# CAN_ESP.net
KiCad netlist of a schematic drawn in Altium Designer
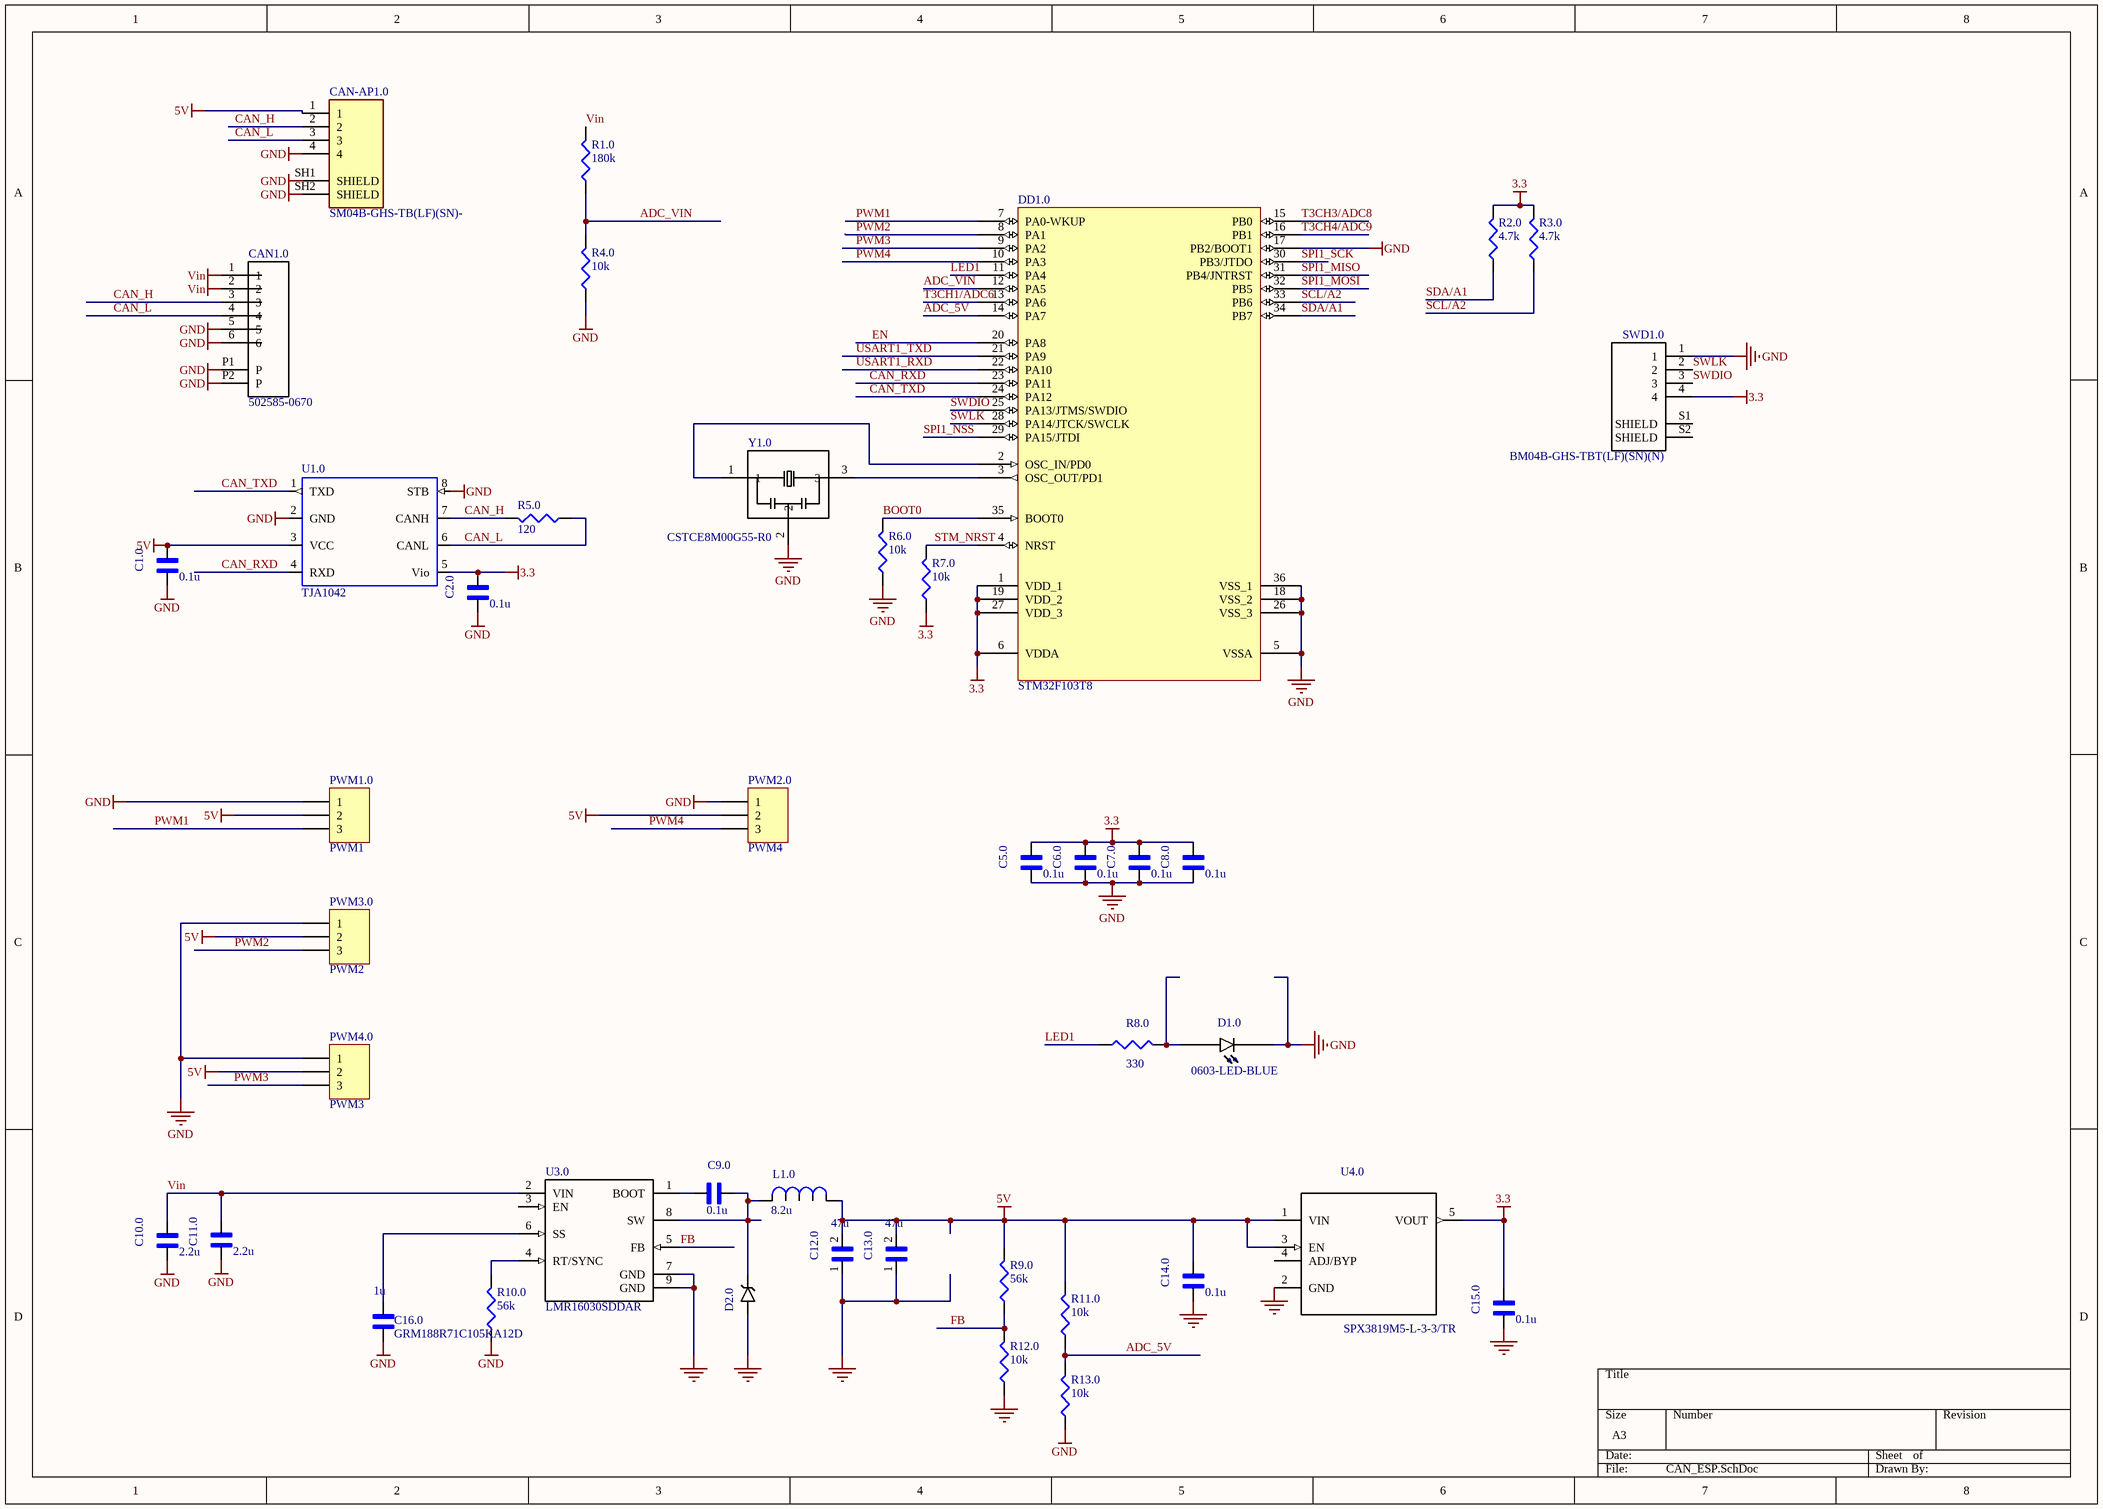
[diagram p0: CAN_ESP.SchDoc]

(export (version "E")
  (design (tool "Eeschema 10.0.6"))
  (components
    (comp (ref "C1.0")
      (value "0.1u")
      (footprint "*CAPC1608X90")
      (description "Cap Thin Film 0.1uf 50v 0603")
      (fields (field (name "MF") "AVX") (field (name "MP") "GX035C104MAT2-500 or CL10B104JB8NNNC"))
      (libsource (lib "lib") (part "GX035C104MAT2-500"))
    )
    (comp (ref "C2.0")
      (value "0.1u")
      (footprint "*CAPC1608X90")
      (description "Cap Thin Film 0.1uf 50v 0603")
      (fields (field (name "MF") "AVX") (field (name "MP") "GX035C104MAT2-500 or CL10B104JB8NNNC"))
      (libsource (lib "lib") (part "GX035C104MAT2-500"))
    )
    (comp (ref "C5.0")
      (value "0.1u")
      (footprint "*CAPC1608X90")
      (description "Cap Thin Film 0.1uf 50v 0603")
      (fields (field (name "MF") "AVX") (field (name "MP") "GX035C104MAT2-500 or CL10B104JB8NNNC"))
      (libsource (lib "lib") (part "GX035C104MAT2-500"))
    )
    (comp (ref "C6.0")
      (value "0.1u")
      (footprint "*CAPC1608X90")
      (description "Cap Thin Film 0.1uf 50v 0603")
      (fields (field (name "MF") "AVX") (field (name "MP") "GX035C104MAT2-500 or CL10B104JB8NNNC"))
      (libsource (lib "lib") (part "GX035C104MAT2-500"))
    )
    (comp (ref "C7.0")
      (value "0.1u")
      (footprint "*CAPC1608X90")
      (description "Cap Thin Film 0.1uf 50v 0603")
      (fields (field (name "MF") "AVX") (field (name "MP") "GX035C104MAT2-500 or CL10B104JB8NNNC"))
      (libsource (lib "lib") (part "GX035C104MAT2-500"))
    )
    (comp (ref "C8.0")
      (value "0.1u")
      (footprint "*CAPC1608X90")
      (description "Cap Thin Film 0.1uf 50v 0603")
      (fields (field (name "MF") "AVX") (field (name "MP") "GX035C104MAT2-500 or CL10B104JB8NNNC"))
      (libsource (lib "lib") (part "GX035C104MAT2-500"))
    )
    (comp (ref "C9.0")
      (value "0.1u")
      (footprint "*CAPC1608X90")
      (description "Cap Thin Film 0.1uf 50v 0603")
      (fields (field (name "MF") "AVX") (field (name "MP") "GX035C104MAT2-500 or CL10B104JB8NNNC"))
      (libsource (lib "lib") (part "GX035C104MAT2-500"))
    )
    (comp (ref "C10.0")
      (value "2.2u")
      (footprint "*CAP3216X125N")
      (description "1206 2.2 uF 50 V В±10% Tolerance X7R SMT Multilayer Ceramic Capacitor")
      (fields (field (name "MF") "Murata Electronics") (field (name "MP") "GRM31CR71H225KA88L"))
      (libsource (lib "lib") (part "GRM31CR71H225KA88L"))
    )
    (comp (ref "C11.0")
      (value "2.2u")
      (footprint "*CAP3216X125N")
      (description "1206 2.2 uF 50 V В±10% Tolerance X7R SMT Multilayer Ceramic Capacitor")
      (fields (field (name "MF") "Murata Electronics") (field (name "MP") "GRM31CR71H225KA88L"))
      (libsource (lib "lib") (part "GRM31CR71H225KA88L"))
    )
    (comp (ref "C12.0")
      (value "47u")
      (footprint "*CAPC3216X125N")
      (description "Multilayer Ceramic Capacitor, GRM Series, 47 - F, - 10%, X5R, 10 V, 1206 [3216 Metric]")
      (fields (field (name "MF") "Murata Electronics") (field (name "MP") "GRM31CR61A476KE15L"))
      (libsource (lib "lib") (part "GRM31CR61A476KE15L"))
    )
    (comp (ref "C13.0")
      (value "47u")
      (footprint "*CAPC3216X125N")
      (description "Multilayer Ceramic Capacitor, GRM Series, 47 - F, - 10%, X5R, 10 V, 1206 [3216 Metric]")
      (fields (field (name "MF") "Murata Electronics") (field (name "MP") "GRM31CR61A476KE15L"))
      (libsource (lib "lib") (part "GRM31CR61A476KE15L"))
    )
    (comp (ref "C14.0")
      (value "0.1u")
      (footprint "*CAPC1608X90")
      (description "Cap Thin Film 0.1uf 50v 0603")
      (fields (field (name "MF") "AVX") (field (name "MP") "GX035C104MAT2-500"))
      (libsource (lib "lib") (part "GX035C104MAT2-500"))
    )
    (comp (ref "C15.0")
      (value "0.1u")
      (footprint "*CAPC1608X90")
      (description "Cap Thin Film 0.1uf 50v 0603")
      (fields (field (name "MF") "AVX") (field (name "MP") "GX035C104MAT2-500"))
      (libsource (lib "lib") (part "GX035C104MAT2-500"))
    )
    (comp (ref "C16.0")
      (value "GRM188R71C105KA12D")
      (footprint "CAPC1608X90N")
      (description "SMD Capacitor X7R(EIA) with Capacitance: 1.0uF Tol. 10%. Rated Voltage: 16Vdc")
      (fields (field (name "MF") "Murata Electronics") (field (name "ALTIUM_VALUE") "1u"))
      (libsource (lib "lib") (part "GRM188R71C105KA12D"))
    )
    (comp (ref "CAN-AP1.0")
      (value "SM04B-GHS-TB(LF)(SN)-")
      (footprint "JST_SM04B-GHS-TB(LF)(SN)-")
      (description "Connector Header Surface Mount, Right Angle 4 position 0.049 _1.25mm_")
      (fields (field (name "MP") "SM04B-GHS-TB(LF)(SN)") (field (name "MF") "JST Sales"))
      (libsource (lib "lib") (part "SM04B-GHS-TB(LF)(SN)-"))
    )
    (comp (ref "CAN1.0")
      (value "502585-0670")
      (footprint "MOLEX_502585-0670")
      (fields (field (name "MF") "Molex"))
      (libsource (lib "lib") (part "502585-0670"))
    )
    (comp (ref "D1.0")
      (value "0603-LED-BLUE")
      (footprint "*LEDM1608X80_LTE-C1906R-14(Primary)")
      (description "LED IrLED Chip LED 2-Pin SMD T/R")
      (libsource (lib "lib") (part "LTE-C1906R-14"))
    )
    (comp (ref "D2.0")
      (value "SK56")
      (footprint "*SMB_P6SMB62AT3G(Primary)")
      (description "Диод Шоттки 5А 60В [SMB / DO-214AA]")
      (fields (field (name "MF") "Littelfuse Inc."))
      (libsource (lib "lib") (part "SK56"))
    )
    (comp (ref "DD1.0")
      (value "STM32F103T8")
      (footprint "*QFN50P600X600X100-37N")
      (description "STM32F103T8U6, Микроконтроллер 32BIT ARM 64K FLASH [VFQFPN-36]")
      (fields (field (name "MF") "STM") (field (name "MP") "STM32F103T8U6"))
      (libsource (lib "lib") (part "STM32F103T8"))
    )
    (comp (ref "L1.0")
      (value "8.2u")
      (footprint "*IND_IHLP_2525_CZ")
      (description "IHLP2525CZER8R2M01, 8.2uH 4A 20% Low Profile High Current SMT Inductor, Индуктивность")
      (fields (field (name "MF") "Vishay Dale") (field (name "MP") "IHLP2525CZER8R2M01"))
      (libsource (lib "lib") (part "IHLP2525CZER8R2M01"))
    )
    (comp (ref "PWM1.0")
      (value "PWM1")
      (footprint "HDR Side 3 pin")
      (description "Header, 4-Pin")
      (fields (field (name "MF") "Connfly electronic (Zhenqin)") (field (name "MP") "PLS-3 (DS1021-1x3)"))
      (libsource (lib "DC_DC") (part "Header 3"))
    )
    (comp (ref "PWM2.0")
      (value "PWM4")
      (footprint "HDR Side 3 pin")
      (description "Header, 4-Pin")
      (fields (field (name "MF") "Connfly electronic (Zhenqin)") (field (name "MP") "PLS-3 (DS1021-1x3)"))
      (libsource (lib "DC_DC") (part "Header 3"))
    )
    (comp (ref "PWM3.0")
      (value "PWM2")
      (footprint "HDR Side 3 pin")
      (description "Header, 4-Pin")
      (fields (field (name "MF") "Connfly electronic (Zhenqin)") (field (name "MP") "PLS-3 (DS1021-1x3)"))
      (libsource (lib "DC_DC") (part "Header 3"))
    )
    (comp (ref "PWM4.0")
      (value "PWM3")
      (footprint "HDR Side 3 pin")
      (description "Header, 4-Pin")
      (fields (field (name "MF") "Connfly electronic (Zhenqin)") (field (name "MP") "PLS-3 (DS1021-1x3)"))
      (libsource (lib "DC_DC") (part "Header 3"))
    )
    (comp (ref "R1.0")
      (value "180k")
      (footprint "J1-0603")
      (description "Resistor")
      (fields (field (name "MP") "180K 1% 0603") (field (name "Comment") "Res3"))
      (libsource (lib "Miscellaneous Devices") (part "Res3"))
    )
    (comp (ref "R2.0")
      (value "4.7k")
      (footprint "J1-0603")
      (description "Resistor")
      (fields (field (name "MP") "4.7K 1% 0603") (field (name "Comment") "Res3"))
      (libsource (lib "Miscellaneous Devices") (part "Res3"))
    )
    (comp (ref "R3.0")
      (value "4.7k")
      (footprint "J1-0603")
      (description "Resistor")
      (fields (field (name "MP") "4.7K 1% 0603") (field (name "Comment") "Res3"))
      (libsource (lib "Miscellaneous Devices") (part "Res3"))
    )
    (comp (ref "R4.0")
      (value "10k")
      (footprint "J1-0603")
      (description "Resistor")
      (fields (field (name "MP") "10K 1% 0603") (field (name "Comment") "Res3"))
      (libsource (lib "Miscellaneous Devices") (part "Res3"))
    )
    (comp (ref "R5.0")
      (value "120")
      (footprint "J1-0603")
      (description "120 Ohms 1 0.1 W 1 10 W Chip Resistor 0603 1608 Metric Thick Film")
      (fields (field (name "MP") "RC0603FR-07120RL") (field (name "Comment") "Res3"))
      (libsource (lib "Miscellaneous Devices") (part "Res3"))
    )
    (comp (ref "R6.0")
      (value "10k")
      (footprint "J1-0603")
      (description "10 kOhms 1 0.1 W 1 10 W Chip Resistor 0603 1608 Metric Thick Film")
      (fields (field (name "MF") "Yageo or NXP") (field (name "MP") "10K 1% 0603"))
      (libsource (lib "CAN_NODE_MINI") (part "RC0603FR-0710KL"))
    )
    (comp (ref "R7.0")
      (value "10k")
      (footprint "J1-0603")
      (description "10 kOhms 1 0.1 W 1 10 W Chip Resistor 0603 1608 Metric Thick Film")
      (fields (field (name "MF") "Yageo or NXP") (field (name "MP") "10K 1% 0603"))
      (libsource (lib "CAN_NODE_MINI") (part "RC0603FR-0710KL"))
    )
    (comp (ref "R8.0")
      (value "330")
      (footprint "J1-0603")
      (description "Resistor")
      (fields (field (name "MP") "RC0603FR-07330RL") (field (name "Comment") "Res3"))
      (libsource (lib "Miscellaneous Devices") (part "Res3"))
    )
    (comp (ref "R9.0")
      (value "56k")
      (footprint "J1-0603")
      (description "Resistor")
      (fields (field (name "MP") "RC0603FR-0756KL") (field (name "Comment") "Res3"))
      (libsource (lib "Miscellaneous Devices") (part "Res3"))
    )
    (comp (ref "R10.0")
      (value "56k")
      (footprint "J1-0603")
      (description "Resistor")
      (fields (field (name "MP") "RC0603FR-0756KL") (field (name "Comment") "Res3"))
      (libsource (lib "Miscellaneous Devices") (part "Res3"))
    )
    (comp (ref "R11.0")
      (value "10k")
      (footprint "J1-0603")
      (description "10 kOhms 1 0.1 W 1 10 W Chip Resistor 0603 1608 Metric Thick Film")
      (fields (field (name "MF") "Yageo or NXP") (field (name "MP") "10K 1% 0603"))
      (libsource (lib "CAN_NODE_MINI") (part "RC0603FR-0710KL"))
    )
    (comp (ref "R12.0")
      (value "10k")
      (footprint "J1-0603")
      (description "10 kOhms 1 0.1 W 1 10 W Chip Resistor 0603 1608 Metric Thick Film")
      (fields (field (name "MF") "Yageo or NXP") (field (name "MP") "10K 1% 0603"))
      (libsource (lib "CAN_NODE_MINI") (part "RC0603FR-0710KL"))
    )
    (comp (ref "R13.0")
      (value "10k")
      (footprint "J1-0603")
      (description "10 kOhms 1 0.1 W 1 10 W Chip Resistor 0603 1608 Metric Thick Film")
      (fields (field (name "MF") "Yageo or NXP") (field (name "MP") "10K 1% 0603"))
      (libsource (lib "CAN_NODE_MINI") (part "RC0603FR-0710KL"))
    )
    (comp (ref "SWD1.0")
      (value "BM04B-GHS-TBT(LF)(SN)(N)")
      (footprint "JST_BM04B-GHS-holes")
      (description "Conn Shrouded Header HDR 4 POS 1.25mm Solder ST SMD Reel")
      (fields (field (name "MF") "JST Sales") (field (name "MP") "SM04B-GHS-TB(LF)(SN)"))
      (libsource (lib "lib") (part "BM04B-GHS-TBT(LF)(SN)(N)"))
    )
    (comp (ref "U1.0")
      (value "TJA1042")
      (footprint "SOT782-1")
      (description "1/1 Transceiver Half CANbus 8-SO")
      (fields (field (name "MF") "NXP USA"))
      (libsource (lib "lib") (part "TJA1042"))
    )
    (comp (ref "U3.0")
      (value "LMR16030SDDAR")
      (footprint "*SOIC127P600X170-9N - duplicate")
      (fields (field (name "MF") "Texas Instruments"))
      (libsource (lib "lib") (part "LMR16030SDDAR"))
    )
    (comp (ref "U4.0")
      (value "SPX3819M5-L-3-3/TR")
      (footprint "*SOT95P280X145-5N")
      (description "Low Dropout Voltage Regulator, Adjustable 0.5A, В±1%, 2.5 to 16 Vin, 5-Pin SOT-23")
      (fields (field (name "MF") "MaxLinear, Inc."))
      (libsource (lib "DC_DC") (part "SPX3819M5-L"))
    )
    (comp (ref "Y1.0")
      (value "CSTCE8M00G55-R0")
      (footprint "*OSC_CSTCE8M00G55-R0")
      (description "Ceramic Resonator 8MHz ??0.5% _Tol_ ??0.2% _Stability_ 33pF 40Ohm 3-Pin CSMD T/R")
      (fields (field (name "MF") "Murata"))
      (libsource (lib "DC_DC") (part "CSTCE8M00G55-R0"))
    )
  )
  (nets
    (net (code "1") (name "/ADC_5V") (class "Default")
      (node (ref "DD1.0") (pin "14") (pinfunction "PA7_14") (pintype "bidirectional"))
      (node (ref "R11.0") (pin "1") (pinfunction "1_1") (pintype "passive"))
      (node (ref "R13.0") (pin "2") (pinfunction "2_2") (pintype "passive"))
    )
    (net (code "2") (name "/ADC_VIN") (class "Default")
      (node (ref "DD1.0") (pin "12") (pinfunction "PA5_12") (pintype "bidirectional"))
      (node (ref "R1.0") (pin "1") (pinfunction "1_1") (pintype "passive"))
      (node (ref "R4.0") (pin "2") (pinfunction "2_2") (pintype "passive"))
    )
    (net (code "3") (name "/BOOT0") (class "Default")
      (node (ref "DD1.0") (pin "35") (pinfunction "BOOT0_35") (pintype "input"))
      (node (ref "R6.0") (pin "2") (pinfunction "2_2") (pintype "passive"))
    )
    (net (code "4") (name "/CAN_H") (class "Default")
      (node (ref "CAN-AP1.0") (pin "2") (pinfunction "2_2") (pintype "passive"))
      (node (ref "CAN1.0") (pin "3") (pinfunction "3_3") (pintype "passive"))
      (node (ref "R5.0") (pin "2") (pinfunction "2_2") (pintype "passive"))
      (node (ref "U1.0") (pin "7") (pinfunction "CANH_7") (pintype "bidirectional"))
    )
    (net (code "5") (name "/CAN_L") (class "Default")
      (node (ref "CAN-AP1.0") (pin "3") (pinfunction "3_3") (pintype "passive"))
      (node (ref "CAN1.0") (pin "4") (pinfunction "4_4") (pintype "passive"))
      (node (ref "R5.0") (pin "1") (pinfunction "1_1") (pintype "passive"))
      (node (ref "U1.0") (pin "6") (pinfunction "CANL_6") (pintype "bidirectional"))
    )
    (net (code "6") (name "/CAN_RXD") (class "Default")
      (node (ref "DD1.0") (pin "23") (pinfunction "PA11_23") (pintype "bidirectional"))
      (node (ref "U1.0") (pin "4") (pinfunction "RXD_4") (pintype "bidirectional"))
    )
    (net (code "7") (name "/CAN_TXD") (class "Default")
      (node (ref "DD1.0") (pin "24") (pinfunction "PA12_24") (pintype "bidirectional"))
      (node (ref "U1.0") (pin "1") (pinfunction "TXD_1") (pintype "output"))
    )
    (net (code "8") (name "/EN") (class "Default")
      (node (ref "DD1.0") (pin "20") (pinfunction "PA8_20") (pintype "bidirectional"))
    )
    (net (code "9") (name "/FB") (class "Default")
      (node (ref "R12.0") (pin "2") (pinfunction "2_2") (pintype "passive"))
      (node (ref "R9.0") (pin "1") (pinfunction "1_1") (pintype "passive"))
      (node (ref "U3.0") (pin "5") (pinfunction "FB_5") (pintype "input"))
    )
    (net (code "10") (name "/LED1") (class "Default")
      (node (ref "DD1.0") (pin "11") (pinfunction "PA4_11") (pintype "bidirectional"))
      (node (ref "R8.0") (pin "1") (pinfunction "1_1") (pintype "passive"))
    )
    (net (code "11") (name "/PWM1") (class "Default")
      (node (ref "DD1.0") (pin "7") (pinfunction "PA0-WKUP_7") (pintype "bidirectional"))
      (node (ref "PWM1.0") (pin "3") (pinfunction "3_3") (pintype "passive"))
    )
    (net (code "12") (name "/PWM2") (class "Default")
      (node (ref "DD1.0") (pin "8") (pinfunction "PA1_8") (pintype "bidirectional"))
      (node (ref "PWM3.0") (pin "3") (pinfunction "3_3") (pintype "passive"))
    )
    (net (code "13") (name "/PWM3") (class "Default")
      (node (ref "DD1.0") (pin "9") (pinfunction "PA2_9") (pintype "bidirectional"))
      (node (ref "PWM4.0") (pin "3") (pinfunction "3_3") (pintype "passive"))
    )
    (net (code "14") (name "/PWM4") (class "Default")
      (node (ref "DD1.0") (pin "10") (pinfunction "PA3_10") (pintype "bidirectional"))
      (node (ref "PWM2.0") (pin "3") (pinfunction "3_3") (pintype "passive"))
    )
    (net (code "15") (name "/SCL{slash}A2") (class "Default")
      (node (ref "DD1.0") (pin "33") (pinfunction "PB6_33") (pintype "bidirectional"))
      (node (ref "R3.0") (pin "1") (pinfunction "1_1") (pintype "passive"))
    )
    (net (code "16") (name "/SDA{slash}A1") (class "Default")
      (node (ref "DD1.0") (pin "34") (pinfunction "PB7_34") (pintype "bidirectional"))
      (node (ref "R2.0") (pin "1") (pinfunction "1_1") (pintype "passive"))
    )
    (net (code "17") (name "/SPI1_MISO") (class "Default")
      (node (ref "DD1.0") (pin "31") (pinfunction "PB4/JNTRST_31") (pintype "bidirectional"))
    )
    (net (code "18") (name "/SPI1_MOSI") (class "Default")
      (node (ref "DD1.0") (pin "32") (pinfunction "PB5_32") (pintype "bidirectional"))
    )
    (net (code "19") (name "/SPI1_NSS") (class "Default")
      (node (ref "DD1.0") (pin "29") (pinfunction "PA15/JTDI_29") (pintype "bidirectional"))
    )
    (net (code "20") (name "/SPI1_SCK") (class "Default")
      (node (ref "DD1.0") (pin "30") (pinfunction "PB3/JTDO_30") (pintype "bidirectional"))
    )
    (net (code "21") (name "/STM_NRST") (class "Default")
      (node (ref "DD1.0") (pin "4") (pinfunction "NRST_4") (pintype "bidirectional"))
      (node (ref "R7.0") (pin "2") (pinfunction "2_2") (pintype "passive"))
    )
    (net (code "22") (name "/SWDIO") (class "Default")
      (node (ref "DD1.0") (pin "25") (pinfunction "PA13/JTMS/SWDIO_25") (pintype "bidirectional"))
      (node (ref "SWD1.0") (pin "3") (pinfunction "3_3") (pintype "passive"))
    )
    (net (code "23") (name "/SWLK") (class "Default")
      (node (ref "DD1.0") (pin "28") (pinfunction "PA14/JTCK/SWCLK_28") (pintype "bidirectional"))
      (node (ref "SWD1.0") (pin "2") (pinfunction "2_2") (pintype "passive"))
    )
    (net (code "24") (name "/T3CH1{slash}ADC6") (class "Default")
      (node (ref "DD1.0") (pin "13") (pinfunction "PA6_13") (pintype "bidirectional"))
    )
    (net (code "25") (name "/T3CH3{slash}ADC8") (class "Default")
      (node (ref "DD1.0") (pin "15") (pinfunction "PB0_15") (pintype "bidirectional"))
    )
    (net (code "26") (name "/T3CH4{slash}ADC9") (class "Default")
      (node (ref "DD1.0") (pin "16") (pinfunction "PB1_16") (pintype "bidirectional"))
    )
    (net (code "27") (name "/USART1_RXD") (class "Default")
      (node (ref "DD1.0") (pin "22") (pinfunction "PA10_22") (pintype "bidirectional"))
    )
    (net (code "28") (name "/USART1_TXD") (class "Default")
      (node (ref "DD1.0") (pin "21") (pinfunction "PA9_21") (pintype "bidirectional"))
    )
    (net (code "29") (name "3.3") (class "Default")
      (node (ref "C15.0") (pin "1") (pinfunction "1_1") (pintype "passive"))
      (node (ref "C2.0") (pin "1") (pinfunction "1_1") (pintype "passive"))
      (node (ref "C5.0") (pin "1") (pinfunction "1_1") (pintype "passive"))
      (node (ref "C6.0") (pin "1") (pinfunction "1_1") (pintype "passive"))
      (node (ref "C7.0") (pin "1") (pinfunction "1_1") (pintype "passive"))
      (node (ref "C8.0") (pin "1") (pinfunction "1_1") (pintype "passive"))
      (node (ref "DD1.0") (pin "1") (pinfunction "VDD_1_1") (pintype "power_in"))
      (node (ref "DD1.0") (pin "19") (pinfunction "VDD_2_19") (pintype "power_in"))
      (node (ref "DD1.0") (pin "27") (pinfunction "VDD_3_27") (pintype "power_in"))
      (node (ref "DD1.0") (pin "6") (pinfunction "VDDA_6") (pintype "power_in"))
      (node (ref "R2.0") (pin "2") (pinfunction "2_2") (pintype "passive"))
      (node (ref "R3.0") (pin "2") (pinfunction "2_2") (pintype "passive"))
      (node (ref "R7.0") (pin "1") (pinfunction "1_1") (pintype "passive"))
      (node (ref "SWD1.0") (pin "4") (pinfunction "4_4") (pintype "passive"))
      (node (ref "U1.0") (pin "5") (pinfunction "Vio_5") (pintype "power_in"))
      (node (ref "U4.0") (pin "5") (pinfunction "VOUT_5") (pintype "output"))
    )
    (net (code "30") (name "5V") (class "Default")
      (node (ref "C1.0") (pin "1") (pinfunction "1_1") (pintype "passive"))
      (node (ref "C12.0") (pin "2") (pinfunction "2_2") (pintype "passive"))
      (node (ref "C13.0") (pin "2") (pinfunction "2_2") (pintype "passive"))
      (node (ref "C14.0") (pin "1") (pinfunction "1_1") (pintype "passive"))
      (node (ref "CAN-AP1.0") (pin "1") (pinfunction "1_1") (pintype "passive"))
      (node (ref "L1.0") (pin "1") (pinfunction "1_1") (pintype "passive"))
      (node (ref "PWM1.0") (pin "2") (pinfunction "2_2") (pintype "passive"))
      (node (ref "PWM2.0") (pin "2") (pinfunction "2_2") (pintype "passive"))
      (node (ref "PWM3.0") (pin "2") (pinfunction "2_2") (pintype "passive"))
      (node (ref "PWM4.0") (pin "2") (pinfunction "2_2") (pintype "passive"))
      (node (ref "R11.0") (pin "2") (pinfunction "2_2") (pintype "passive"))
      (node (ref "R9.0") (pin "2") (pinfunction "2_2") (pintype "passive"))
      (node (ref "U1.0") (pin "3") (pinfunction "VCC_3") (pintype "power_in"))
      (node (ref "U4.0") (pin "1") (pinfunction "VIN_1") (pintype "power_in"))
      (node (ref "U4.0") (pin "3") (pinfunction "EN_3") (pintype "input"))
    )
    (net (code "31") (name "GND") (class "Default")
      (node (ref "C1.0") (pin "2") (pinfunction "2_2") (pintype "passive"))
      (node (ref "C10.0") (pin "2") (pinfunction "2_2") (pintype "passive"))
      (node (ref "C11.0") (pin "2") (pinfunction "2_2") (pintype "passive"))
      (node (ref "C12.0") (pin "1") (pinfunction "1_1") (pintype "passive"))
      (node (ref "C13.0") (pin "1") (pinfunction "1_1") (pintype "passive"))
      (node (ref "C14.0") (pin "2") (pinfunction "2_2") (pintype "passive"))
      (node (ref "C15.0") (pin "2") (pinfunction "2_2") (pintype "passive"))
      (node (ref "C16.0") (pin "1") (pinfunction "1_1") (pintype "passive"))
      (node (ref "C2.0") (pin "2") (pinfunction "2_2") (pintype "passive"))
      (node (ref "C5.0") (pin "2") (pinfunction "2_2") (pintype "passive"))
      (node (ref "C6.0") (pin "2") (pinfunction "2_2") (pintype "passive"))
      (node (ref "C7.0") (pin "2") (pinfunction "2_2") (pintype "passive"))
      (node (ref "C8.0") (pin "2") (pinfunction "2_2") (pintype "passive"))
      (node (ref "CAN-AP1.0") (pin "4") (pinfunction "4_4") (pintype "passive"))
      (node (ref "CAN-AP1.0") (pin "SH1") (pinfunction "SHIELD_SH1") (pintype "power_in"))
      (node (ref "CAN-AP1.0") (pin "SH2") (pinfunction "SHIELD_SH2") (pintype "power_in"))
      (node (ref "CAN1.0") (pin "5") (pinfunction "5_5") (pintype "passive"))
      (node (ref "CAN1.0") (pin "6") (pinfunction "6_6") (pintype "passive"))
      (node (ref "CAN1.0") (pin "P1") (pinfunction "P_P1") (pintype "passive"))
      (node (ref "CAN1.0") (pin "P2") (pinfunction "P_P2") (pintype "passive"))
      (node (ref "D1.0") (pin "C") (pinfunction "C_C") (pintype "passive"))
      (node (ref "D2.0") (pin "A") (pinfunction "A_A") (pintype "power_in"))
      (node (ref "DD1.0") (pin "17") (pinfunction "PB2/BOOT1_17") (pintype "bidirectional"))
      (node (ref "DD1.0") (pin "18") (pinfunction "VSS_2_18") (pintype "power_in"))
      (node (ref "DD1.0") (pin "26") (pinfunction "VSS_3_26") (pintype "power_in"))
      (node (ref "DD1.0") (pin "36") (pinfunction "VSS_1_36") (pintype "power_in"))
      (node (ref "DD1.0") (pin "5") (pinfunction "VSSA_5") (pintype "power_in"))
      (node (ref "PWM1.0") (pin "1") (pinfunction "1_1") (pintype "passive"))
      (node (ref "PWM2.0") (pin "1") (pinfunction "1_1") (pintype "passive"))
      (node (ref "PWM3.0") (pin "1") (pinfunction "1_1") (pintype "passive"))
      (node (ref "PWM4.0") (pin "1") (pinfunction "1_1") (pintype "passive"))
      (node (ref "R10.0") (pin "1") (pinfunction "1_1") (pintype "passive"))
      (node (ref "R12.0") (pin "1") (pinfunction "1_1") (pintype "passive"))
      (node (ref "R13.0") (pin "1") (pinfunction "1_1") (pintype "passive"))
      (node (ref "R4.0") (pin "1") (pinfunction "1_1") (pintype "passive"))
      (node (ref "R6.0") (pin "1") (pinfunction "1_1") (pintype "passive"))
      (node (ref "SWD1.0") (pin "1") (pinfunction "1_1") (pintype "passive"))
      (node (ref "U1.0") (pin "2") (pinfunction "GND_2") (pintype "power_in"))
      (node (ref "U1.0") (pin "8") (pinfunction "STB_8") (pintype "input"))
      (node (ref "U3.0") (pin "7") (pinfunction "GND_7") (pintype "power_in"))
      (node (ref "U3.0") (pin "9") (pinfunction "GND_9") (pintype "power_in"))
      (node (ref "U4.0") (pin "2") (pinfunction "GND_2") (pintype "passive"))
      (node (ref "Y1.0") (pin "2") (pinfunction "2_2") (pintype "power_in"))
    )
    (net (code "32") (name "Net-(D1.0-PadA)") (class "Default")
      (node (ref "D1.0") (pin "A") (pinfunction "A_A") (pintype "passive"))
      (node (ref "R8.0") (pin "2") (pinfunction "2_2") (pintype "passive"))
    )
    (net (code "33") (name "Net-(DD1.0-OSC_IN{slash}PD0)") (class "Default")
      (node (ref "DD1.0") (pin "2") (pinfunction "OSC_IN/PD0_2") (pintype "input"))
      (node (ref "Y1.0") (pin "1") (pinfunction "1_1") (pintype "passive"))
    )
    (net (code "34") (name "Net-(DD1.0-OSC_OUT{slash}PD1)") (class "Default")
      (node (ref "DD1.0") (pin "3") (pinfunction "OSC_OUT/PD1_3") (pintype "output"))
      (node (ref "Y1.0") (pin "3") (pinfunction "3_3") (pintype "passive"))
    )
    (net (code "35") (name "Net-(U3.0-BOOT)") (class "Default")
      (node (ref "C9.0") (pin "2") (pinfunction "2_2") (pintype "passive"))
      (node (ref "U3.0") (pin "1") (pinfunction "BOOT_1") (pintype "power_in"))
    )
    (net (code "36") (name "Net-(U3.0-RT{slash}SYNC)") (class "Default")
      (node (ref "R10.0") (pin "2") (pinfunction "2_2") (pintype "passive"))
      (node (ref "U3.0") (pin "4") (pinfunction "RT/SYNC_4") (pintype "input"))
    )
    (net (code "37") (name "Net-(U3.0-SS)") (class "Default")
      (node (ref "C16.0") (pin "2") (pinfunction "2_2") (pintype "passive"))
      (node (ref "U3.0") (pin "6") (pinfunction "SS_6") (pintype "input"))
    )
    (net (code "38") (name "Net-(U3.0-SW)") (class "Default")
      (node (ref "C9.0") (pin "1") (pinfunction "1_1") (pintype "passive"))
      (node (ref "D2.0") (pin "C") (pinfunction "C_C") (pintype "power_in"))
      (node (ref "L1.0") (pin "2") (pinfunction "2_2") (pintype "passive"))
      (node (ref "U3.0") (pin "8") (pinfunction "SW_8") (pintype "power_in"))
    )
    (net (code "39") (name "Vin") (class "Default")
      (node (ref "C10.0") (pin "1") (pinfunction "1_1") (pintype "passive"))
      (node (ref "C11.0") (pin "1") (pinfunction "1_1") (pintype "passive"))
      (node (ref "CAN1.0") (pin "1") (pinfunction "1_1") (pintype "passive"))
      (node (ref "CAN1.0") (pin "2") (pinfunction "2_2") (pintype "passive"))
      (node (ref "R1.0") (pin "2") (pinfunction "2_2") (pintype "passive"))
      (node (ref "U3.0") (pin "2") (pinfunction "VIN_2") (pintype "power_in"))
    )
    (net (code "40") (name "unconnected-(SWD1.0-SHIELD-PadS1)") (class "Default")
      (node (ref "SWD1.0") (pin "S1") (pinfunction "SHIELD_S1") (pintype "passive"))
    )
    (net (code "41") (name "unconnected-(SWD1.0-SHIELD-PadS2)") (class "Default")
      (node (ref "SWD1.0") (pin "S2") (pinfunction "SHIELD_S2") (pintype "passive"))
    )
    (net (code "42") (name "unconnected-(U3.0-EN-Pad3)") (class "Default")
      (node (ref "U3.0") (pin "3") (pinfunction "EN_3") (pintype "input"))
    )
    (net (code "43") (name "unconnected-(U4.0-ADJ{slash}BYP-Pad4)") (class "Default")
      (node (ref "U4.0") (pin "4") (pinfunction "ADJ/BYP_4") (pintype "passive"))
    )
  )
)
